# HVAC8.net
KiCad netlist of a schematic drawn in EAGLE
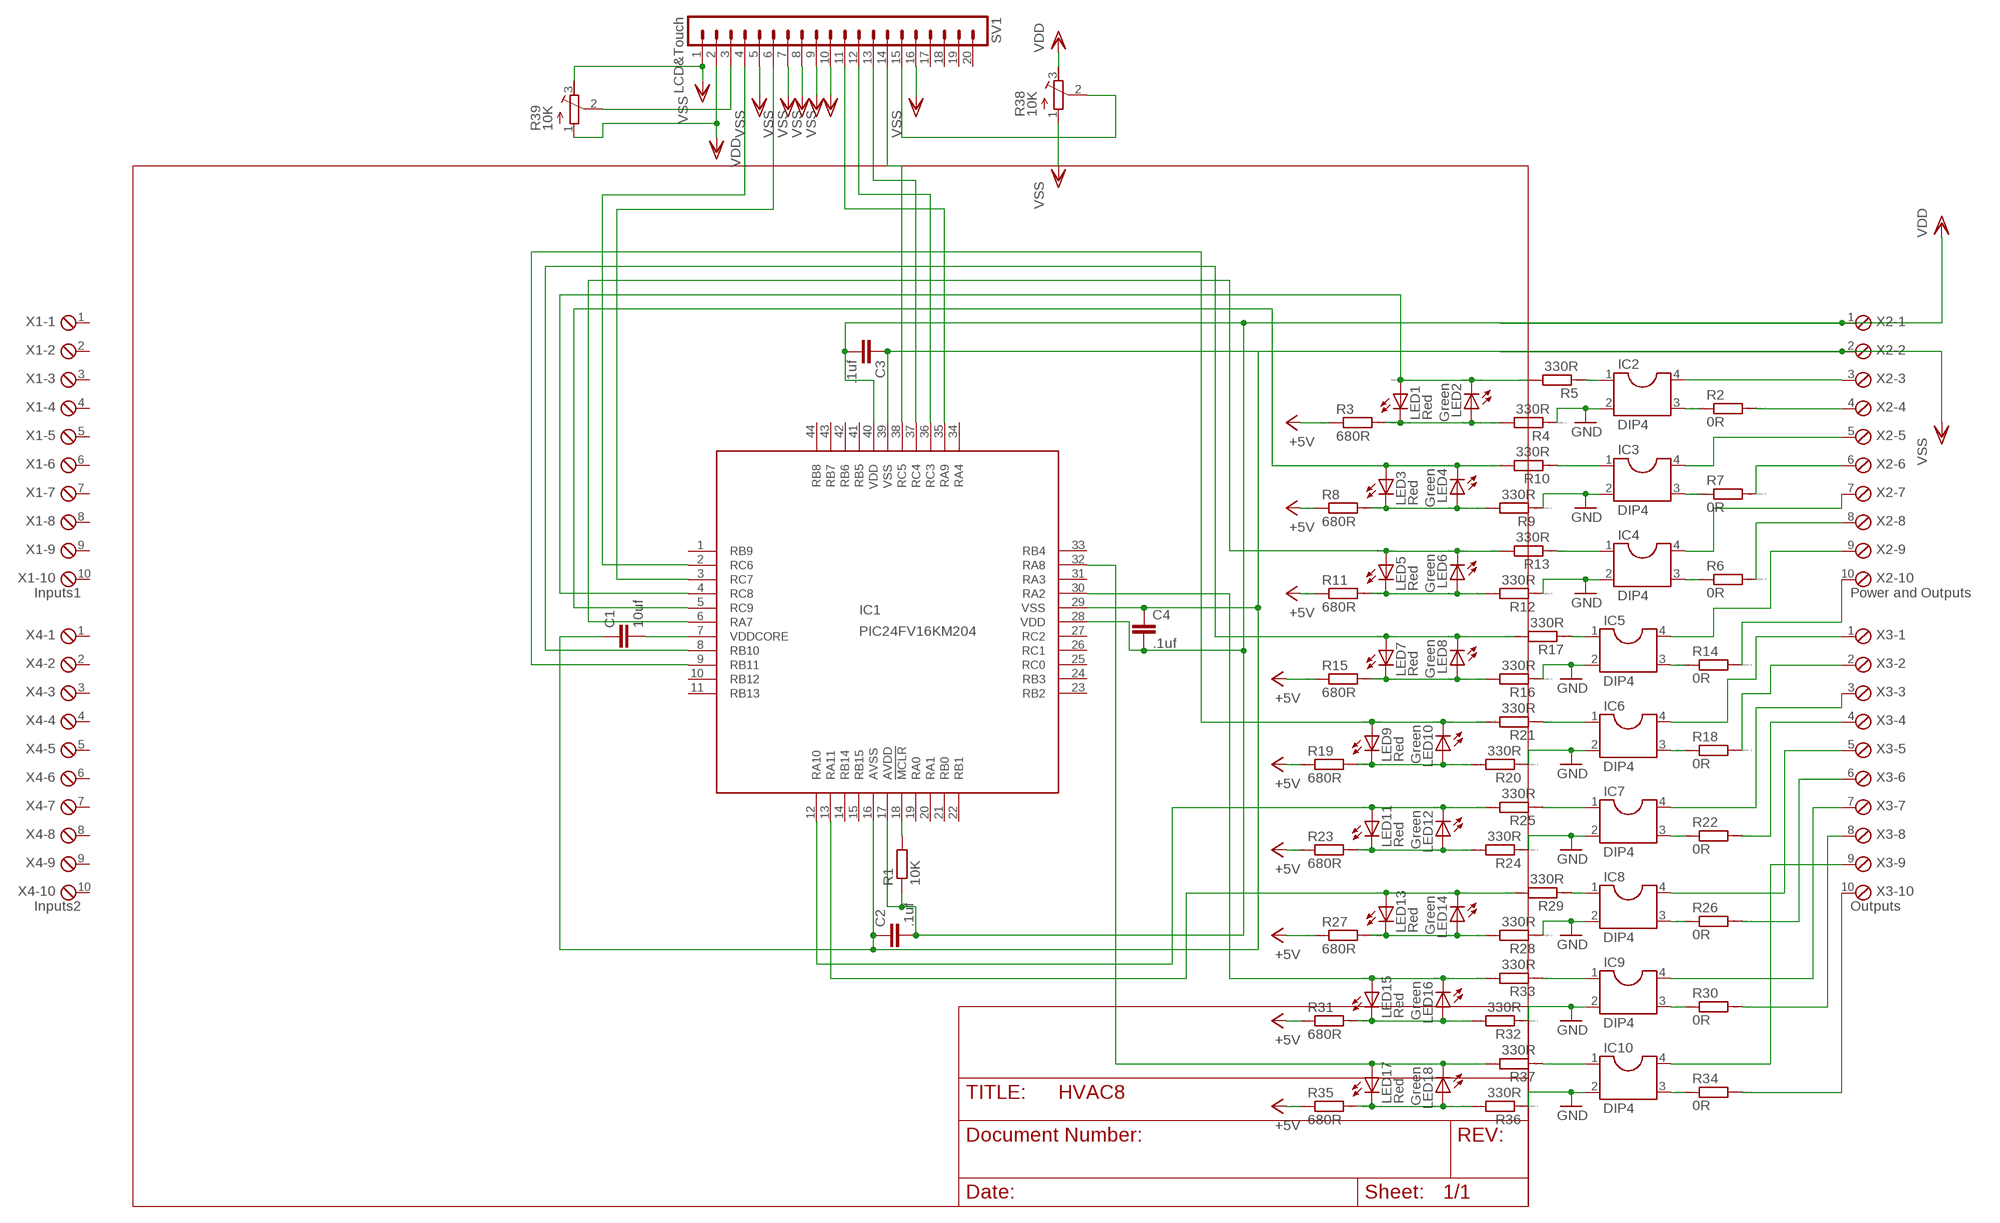
[diagram p0: schematic, sheet 1]

(export (version "E")
  (design (tool "Eeschema 10.0.6"))
  (components
    (comp (ref "C1")
      (value "10uf")
      (footprint "eagle-import:C1206")
      (libsource (lib "eagle-import") (part "C-EUC1206"))
    )
    (comp (ref "C2")
      (value ".1uf")
      (footprint "eagle-import:C1206")
      (libsource (lib "eagle-import") (part "C-EUC1206"))
    )
    (comp (ref "C3")
      (value ".1uf")
      (footprint "eagle-import:C1206")
      (libsource (lib "eagle-import") (part "C-EUC1206"))
    )
    (comp (ref "C4")
      (value ".1uf")
      (footprint "eagle-import:C1206")
      (libsource (lib "eagle-import") (part "C-EUC1206"))
    )
    (comp (ref "IC1")
      (value "PIC24FV16KM204")
      (footprint "eagle-import:TQFP44")
      (libsource (lib "eagle-import") (part "PIC24FV16KM204"))
    )
    (comp (ref "IC2")
      (value "DIP4")
      (footprint "eagle-import:SOCKET-04")
      (libsource (lib "eagle-import") (part "DIL4S"))
    )
    (comp (ref "IC3")
      (value "DIP4")
      (footprint "eagle-import:SOCKET-04")
      (libsource (lib "eagle-import") (part "DIL4S"))
    )
    (comp (ref "IC4")
      (value "DIP4")
      (footprint "eagle-import:SOCKET-04")
      (libsource (lib "eagle-import") (part "DIL4S"))
    )
    (comp (ref "IC5")
      (value "DIP4")
      (footprint "eagle-import:SOCKET-04")
      (libsource (lib "eagle-import") (part "DIL4S"))
    )
    (comp (ref "IC6")
      (value "DIP4")
      (footprint "eagle-import:SOCKET-04")
      (libsource (lib "eagle-import") (part "DIL4S"))
    )
    (comp (ref "IC7")
      (value "DIP4")
      (footprint "eagle-import:SOCKET-04")
      (libsource (lib "eagle-import") (part "DIL4S"))
    )
    (comp (ref "IC8")
      (value "DIP4")
      (footprint "eagle-import:SOCKET-04")
      (libsource (lib "eagle-import") (part "DIL4S"))
    )
    (comp (ref "IC9")
      (value "DIP4")
      (footprint "eagle-import:SOCKET-04")
      (libsource (lib "eagle-import") (part "DIL4S"))
    )
    (comp (ref "IC10")
      (value "DIP4")
      (footprint "eagle-import:SOCKET-04")
      (libsource (lib "eagle-import") (part "DIL4S"))
    )
    (comp (ref "LED1")
      (value "Red")
      (footprint "eagle-import:LED_1206")
      (libsource (lib "eagle-import") (part "LED_E"))
    )
    (comp (ref "LED2")
      (value "Green")
      (footprint "eagle-import:LED_1206")
      (libsource (lib "eagle-import") (part "LED_E"))
    )
    (comp (ref "LED3")
      (value "Red")
      (footprint "eagle-import:LED_1206")
      (libsource (lib "eagle-import") (part "LED_E"))
    )
    (comp (ref "LED4")
      (value "Green")
      (footprint "eagle-import:LED_1206")
      (libsource (lib "eagle-import") (part "LED_E"))
    )
    (comp (ref "LED5")
      (value "Red")
      (footprint "eagle-import:LED_1206")
      (libsource (lib "eagle-import") (part "LED_E"))
    )
    (comp (ref "LED6")
      (value "Green")
      (footprint "eagle-import:LED_1206")
      (libsource (lib "eagle-import") (part "LED_E"))
    )
    (comp (ref "LED7")
      (value "Red")
      (footprint "eagle-import:LED_1206")
      (libsource (lib "eagle-import") (part "LED_E"))
    )
    (comp (ref "LED8")
      (value "Green")
      (footprint "eagle-import:LED_1206")
      (libsource (lib "eagle-import") (part "LED_E"))
    )
    (comp (ref "LED9")
      (value "Red")
      (footprint "eagle-import:LED_1206")
      (libsource (lib "eagle-import") (part "LED_E"))
    )
    (comp (ref "LED10")
      (value "Green")
      (footprint "eagle-import:LED_1206")
      (libsource (lib "eagle-import") (part "LED_E"))
    )
    (comp (ref "LED11")
      (value "Red")
      (footprint "eagle-import:LED_1206")
      (libsource (lib "eagle-import") (part "LED_E"))
    )
    (comp (ref "LED12")
      (value "Green")
      (footprint "eagle-import:LED_1206")
      (libsource (lib "eagle-import") (part "LED_E"))
    )
    (comp (ref "LED13")
      (value "Red")
      (footprint "eagle-import:LED_1206")
      (libsource (lib "eagle-import") (part "LED_E"))
    )
    (comp (ref "LED14")
      (value "Green")
      (footprint "eagle-import:LED_1206")
      (libsource (lib "eagle-import") (part "LED_E"))
    )
    (comp (ref "LED15")
      (value "Red")
      (footprint "eagle-import:LED_1206")
      (libsource (lib "eagle-import") (part "LED_E"))
    )
    (comp (ref "LED16")
      (value "Green")
      (footprint "eagle-import:LED_1206")
      (libsource (lib "eagle-import") (part "LED_E"))
    )
    (comp (ref "LED17")
      (value "Red")
      (footprint "eagle-import:LED_1206")
      (libsource (lib "eagle-import") (part "LED_E"))
    )
    (comp (ref "LED18")
      (value "Green")
      (footprint "eagle-import:LED_1206")
      (libsource (lib "eagle-import") (part "LED_E"))
    )
    (comp (ref "R1")
      (value "10K")
      (footprint "eagle-import:R1206")
      (libsource (lib "eagle-import") (part "R-EU_R1206"))
    )
    (comp (ref "R2")
      (value "0R")
      (footprint "eagle-import:R1206")
      (libsource (lib "eagle-import") (part "RR1206"))
    )
    (comp (ref "R3")
      (value "680R")
      (footprint "eagle-import:R1206")
      (libsource (lib "eagle-import") (part "RR1206"))
    )
    (comp (ref "R4")
      (value "330R")
      (footprint "eagle-import:R1206")
      (libsource (lib "eagle-import") (part "RR1206"))
    )
    (comp (ref "R5")
      (value "330R")
      (footprint "eagle-import:R1206")
      (libsource (lib "eagle-import") (part "RR1206"))
    )
    (comp (ref "R6")
      (value "0R")
      (footprint "eagle-import:R1206")
      (libsource (lib "eagle-import") (part "RR1206"))
    )
    (comp (ref "R7")
      (value "0R")
      (footprint "eagle-import:R1206")
      (libsource (lib "eagle-import") (part "RR1206"))
    )
    (comp (ref "R8")
      (value "680R")
      (footprint "eagle-import:R1206")
      (libsource (lib "eagle-import") (part "RR1206"))
    )
    (comp (ref "R9")
      (value "330R")
      (footprint "eagle-import:R1206")
      (libsource (lib "eagle-import") (part "RR1206"))
    )
    (comp (ref "R10")
      (value "330R")
      (footprint "eagle-import:R1206")
      (libsource (lib "eagle-import") (part "RR1206"))
    )
    (comp (ref "R11")
      (value "680R")
      (footprint "eagle-import:R1206")
      (libsource (lib "eagle-import") (part "RR1206"))
    )
    (comp (ref "R12")
      (value "330R")
      (footprint "eagle-import:R1206")
      (libsource (lib "eagle-import") (part "RR1206"))
    )
    (comp (ref "R13")
      (value "330R")
      (footprint "eagle-import:R1206")
      (libsource (lib "eagle-import") (part "RR1206"))
    )
    (comp (ref "R14")
      (value "0R")
      (footprint "eagle-import:R1206")
      (libsource (lib "eagle-import") (part "RR1206"))
    )
    (comp (ref "R15")
      (value "680R")
      (footprint "eagle-import:R1206")
      (libsource (lib "eagle-import") (part "RR1206"))
    )
    (comp (ref "R16")
      (value "330R")
      (footprint "eagle-import:R1206")
      (libsource (lib "eagle-import") (part "RR1206"))
    )
    (comp (ref "R17")
      (value "330R")
      (footprint "eagle-import:R1206")
      (libsource (lib "eagle-import") (part "RR1206"))
    )
    (comp (ref "R18")
      (value "0R")
      (footprint "eagle-import:R1206")
      (libsource (lib "eagle-import") (part "RR1206"))
    )
    (comp (ref "R19")
      (value "680R")
      (footprint "eagle-import:R1206")
      (libsource (lib "eagle-import") (part "RR1206"))
    )
    (comp (ref "R20")
      (value "330R")
      (footprint "eagle-import:R1206")
      (libsource (lib "eagle-import") (part "RR1206"))
    )
    (comp (ref "R21")
      (value "330R")
      (footprint "eagle-import:R1206")
      (libsource (lib "eagle-import") (part "RR1206"))
    )
    (comp (ref "R22")
      (value "0R")
      (footprint "eagle-import:R1206")
      (libsource (lib "eagle-import") (part "RR1206"))
    )
    (comp (ref "R23")
      (value "680R")
      (footprint "eagle-import:R1206")
      (libsource (lib "eagle-import") (part "RR1206"))
    )
    (comp (ref "R24")
      (value "330R")
      (footprint "eagle-import:R1206")
      (libsource (lib "eagle-import") (part "RR1206"))
    )
    (comp (ref "R25")
      (value "330R")
      (footprint "eagle-import:R1206")
      (libsource (lib "eagle-import") (part "RR1206"))
    )
    (comp (ref "R26")
      (value "0R")
      (footprint "eagle-import:R1206")
      (libsource (lib "eagle-import") (part "RR1206"))
    )
    (comp (ref "R27")
      (value "680R")
      (footprint "eagle-import:R1206")
      (libsource (lib "eagle-import") (part "RR1206"))
    )
    (comp (ref "R28")
      (value "330R")
      (footprint "eagle-import:R1206")
      (libsource (lib "eagle-import") (part "RR1206"))
    )
    (comp (ref "R29")
      (value "330R")
      (footprint "eagle-import:R1206")
      (libsource (lib "eagle-import") (part "RR1206"))
    )
    (comp (ref "R30")
      (value "0R")
      (footprint "eagle-import:R1206")
      (libsource (lib "eagle-import") (part "RR1206"))
    )
    (comp (ref "R31")
      (value "680R")
      (footprint "eagle-import:R1206")
      (libsource (lib "eagle-import") (part "RR1206"))
    )
    (comp (ref "R32")
      (value "330R")
      (footprint "eagle-import:R1206")
      (libsource (lib "eagle-import") (part "RR1206"))
    )
    (comp (ref "R33")
      (value "330R")
      (footprint "eagle-import:R1206")
      (libsource (lib "eagle-import") (part "RR1206"))
    )
    (comp (ref "R34")
      (value "0R")
      (footprint "eagle-import:R1206")
      (libsource (lib "eagle-import") (part "RR1206"))
    )
    (comp (ref "R35")
      (value "680R")
      (footprint "eagle-import:R1206")
      (libsource (lib "eagle-import") (part "RR1206"))
    )
    (comp (ref "R36")
      (value "330R")
      (footprint "eagle-import:R1206")
      (libsource (lib "eagle-import") (part "RR1206"))
    )
    (comp (ref "R37")
      (value "330R")
      (footprint "eagle-import:R1206")
      (libsource (lib "eagle-import") (part "RR1206"))
    )
    (comp (ref "R38")
      (value "10K")
      (footprint "eagle-import:RTRIM3296W")
      (libsource (lib "eagle-import") (part "R-TRIMM3296W"))
    )
    (comp (ref "R39")
      (value "10K")
      (footprint "eagle-import:RTRIM3296W")
      (libsource (lib "eagle-import") (part "R-TRIMM3296W"))
    )
    (comp (ref "SV1")
      (value "LCD&Touch")
      (footprint "eagle-import:MA20-1")
      (libsource (lib "eagle-import") (part "MA20-1"))
    )
    (comp (ref "X1")
      (value "Inputs1")
      (footprint "eagle-import:10POL254")
      (libsource (lib "eagle-import") (part "MPT10"))
    )
    (comp (ref "X2")
      (value "Power and Outputs")
      (footprint "eagle-import:10POL254")
      (libsource (lib "eagle-import") (part "MPT10"))
    )
    (comp (ref "X3")
      (value "Outputs")
      (footprint "eagle-import:10POL254")
      (libsource (lib "eagle-import") (part "MPT10"))
    )
    (comp (ref "X4")
      (value "Inputs2")
      (footprint "eagle-import:10POL254")
      (libsource (lib "eagle-import") (part "MPT10"))
    )
  )
  (nets
    (net (code "1") (name "+5V") (class "Default")
      (node (ref "R11") (pin "1") (pinfunction "1_1") (pintype "passive"))
      (node (ref "R15") (pin "1") (pinfunction "1_1") (pintype "passive"))
      (node (ref "R19") (pin "1") (pinfunction "1_1") (pintype "passive"))
      (node (ref "R23") (pin "1") (pinfunction "1_1") (pintype "passive"))
      (node (ref "R27") (pin "1") (pinfunction "1_1") (pintype "passive"))
      (node (ref "R3") (pin "1") (pinfunction "1_1") (pintype "passive"))
      (node (ref "R31") (pin "1") (pinfunction "1_1") (pintype "passive"))
      (node (ref "R35") (pin "1") (pinfunction "1_1") (pintype "passive"))
      (node (ref "R8") (pin "1") (pinfunction "1_1") (pintype "passive"))
    )
    (net (code "2") (name "GND") (class "Default")
      (node (ref "IC10") (pin "2") (pinfunction "2_2") (pintype "passive"))
      (node (ref "IC2") (pin "2") (pinfunction "2_2") (pintype "passive"))
      (node (ref "IC3") (pin "2") (pinfunction "2_2") (pintype "passive"))
      (node (ref "IC4") (pin "2") (pinfunction "2_2") (pintype "passive"))
      (node (ref "IC5") (pin "2") (pinfunction "2_2") (pintype "passive"))
      (node (ref "IC6") (pin "2") (pinfunction "2_2") (pintype "passive"))
      (node (ref "IC7") (pin "2") (pinfunction "2_2") (pintype "passive"))
      (node (ref "IC8") (pin "2") (pinfunction "2_2") (pintype "passive"))
      (node (ref "IC9") (pin "2") (pinfunction "2_2") (pintype "passive"))
      (node (ref "R12") (pin "1") (pinfunction "1_1") (pintype "passive"))
      (node (ref "R16") (pin "1") (pinfunction "1_1") (pintype "passive"))
      (node (ref "R20") (pin "1") (pinfunction "1_1") (pintype "passive"))
      (node (ref "R24") (pin "1") (pinfunction "1_1") (pintype "passive"))
      (node (ref "R28") (pin "1") (pinfunction "1_1") (pintype "passive"))
      (node (ref "R32") (pin "1") (pinfunction "1_1") (pintype "passive"))
      (node (ref "R36") (pin "1") (pinfunction "1_1") (pintype "passive"))
      (node (ref "R4") (pin "1") (pinfunction "1_1") (pintype "passive"))
      (node (ref "R9") (pin "1") (pinfunction "1_1") (pintype "passive"))
    )
    (net (code "3") (name "Net-(IC1-RA2)") (class "Default")
      (node (ref "IC1") (pin "30") (pinfunction "RA2_30") (pintype "bidirectional"))
      (node (ref "LED15") (pin "A") (pinfunction "A_A") (pintype "passive"))
      (node (ref "LED16") (pin "C") (pinfunction "C_C") (pintype "passive"))
      (node (ref "R33") (pin "2") (pinfunction "2_2") (pintype "passive"))
    )
    (net (code "4") (name "Net-(IC1-RA7)") (class "Default")
      (node (ref "IC1") (pin "6") (pinfunction "RA7_6") (pintype "bidirectional"))
      (node (ref "LED5") (pin "A") (pinfunction "A_A") (pintype "passive"))
      (node (ref "LED6") (pin "C") (pinfunction "C_C") (pintype "passive"))
      (node (ref "R13") (pin "2") (pinfunction "2_2") (pintype "passive"))
    )
    (net (code "5") (name "Net-(IC1-RA8)") (class "Default")
      (node (ref "IC1") (pin "32") (pinfunction "RA8_32") (pintype "bidirectional"))
      (node (ref "LED17") (pin "A") (pinfunction "A_A") (pintype "passive"))
      (node (ref "LED18") (pin "C") (pinfunction "C_C") (pintype "passive"))
      (node (ref "R37") (pin "2") (pinfunction "2_2") (pintype "passive"))
    )
    (net (code "6") (name "Net-(IC1-RA9)") (class "Default")
      (node (ref "IC1") (pin "35") (pinfunction "RA9_35") (pintype "bidirectional"))
      (node (ref "SV1") (pin "11") (pinfunction "11_11") (pintype "passive"))
    )
    (net (code "7") (name "Net-(IC1-RA10)") (class "Default")
      (node (ref "IC1") (pin "12") (pinfunction "RA10_12") (pintype "bidirectional"))
      (node (ref "LED11") (pin "A") (pinfunction "A_A") (pintype "passive"))
      (node (ref "LED12") (pin "C") (pinfunction "C_C") (pintype "passive"))
      (node (ref "R25") (pin "2") (pinfunction "2_2") (pintype "passive"))
    )
    (net (code "8") (name "Net-(IC1-RA11)") (class "Default")
      (node (ref "IC1") (pin "13") (pinfunction "RA11_13") (pintype "bidirectional"))
      (node (ref "LED13") (pin "A") (pinfunction "A_A") (pintype "passive"))
      (node (ref "LED14") (pin "C") (pinfunction "C_C") (pintype "passive"))
      (node (ref "R29") (pin "2") (pinfunction "2_2") (pintype "passive"))
    )
    (net (code "9") (name "Net-(IC1-RB10)") (class "Default")
      (node (ref "IC1") (pin "8") (pinfunction "RB10_8") (pintype "bidirectional"))
      (node (ref "LED7") (pin "A") (pinfunction "A_A") (pintype "passive"))
      (node (ref "LED8") (pin "C") (pinfunction "C_C") (pintype "passive"))
      (node (ref "R17") (pin "2") (pinfunction "2_2") (pintype "passive"))
    )
    (net (code "10") (name "Net-(IC1-RB11)") (class "Default")
      (node (ref "IC1") (pin "9") (pinfunction "RB11_9") (pintype "bidirectional"))
      (node (ref "LED10") (pin "C") (pinfunction "C_C") (pintype "passive"))
      (node (ref "LED9") (pin "A") (pinfunction "A_A") (pintype "passive"))
      (node (ref "R21") (pin "2") (pinfunction "2_2") (pintype "passive"))
    )
    (net (code "11") (name "Net-(IC1-RC3)") (class "Default")
      (node (ref "IC1") (pin "36") (pinfunction "RC3_36") (pintype "bidirectional"))
      (node (ref "SV1") (pin "12") (pinfunction "12_12") (pintype "passive"))
    )
    (net (code "12") (name "Net-(IC1-RC4)") (class "Default")
      (node (ref "IC1") (pin "37") (pinfunction "RC4_37") (pintype "bidirectional"))
      (node (ref "SV1") (pin "13") (pinfunction "13_13") (pintype "passive"))
    )
    (net (code "13") (name "Net-(IC1-RC5)") (class "Default")
      (node (ref "IC1") (pin "38") (pinfunction "RC5_38") (pintype "bidirectional"))
      (node (ref "SV1") (pin "14") (pinfunction "14_14") (pintype "passive"))
    )
    (net (code "14") (name "Net-(IC1-RC6)") (class "Default")
      (node (ref "IC1") (pin "2") (pinfunction "RC6_2") (pintype "bidirectional"))
      (node (ref "SV1") (pin "4") (pinfunction "4_4") (pintype "passive"))
    )
    (net (code "15") (name "Net-(IC1-RC7)") (class "Default")
      (node (ref "IC1") (pin "3") (pinfunction "RC7_3") (pintype "bidirectional"))
      (node (ref "SV1") (pin "6") (pinfunction "6_6") (pintype "passive"))
    )
    (net (code "16") (name "Net-(IC1-RC8)") (class "Default")
      (node (ref "IC1") (pin "4") (pinfunction "RC8_4") (pintype "bidirectional"))
      (node (ref "LED1") (pin "A") (pinfunction "A_A") (pintype "passive"))
      (node (ref "LED2") (pin "C") (pinfunction "C_C") (pintype "passive"))
      (node (ref "R5") (pin "2") (pinfunction "2_2") (pintype "passive"))
    )
    (net (code "17") (name "Net-(IC1-RC9)") (class "Default")
      (node (ref "IC1") (pin "5") (pinfunction "RC9_5") (pintype "bidirectional"))
      (node (ref "LED3") (pin "A") (pinfunction "A_A") (pintype "passive"))
      (node (ref "LED4") (pin "C") (pinfunction "C_C") (pintype "passive"))
      (node (ref "R10") (pin "2") (pinfunction "2_2") (pintype "passive"))
    )
    (net (code "18") (name "Net-(IC1-VDDCORE)") (class "Default")
      (node (ref "C1") (pin "2") (pinfunction "2_2") (pintype "passive"))
      (node (ref "IC1") (pin "7") (pinfunction "VDDCORE_7") (pintype "power_in"))
    )
    (net (code "19") (name "Net-(IC1-~{MCLR})") (class "Default")
      (node (ref "IC1") (pin "18") (pinfunction "~{MCLR}_18") (pintype "bidirectional"))
      (node (ref "R1") (pin "2") (pinfunction "2_2") (pintype "passive"))
    )
    (net (code "20") (name "Net-(IC2-Pad1)") (class "Default")
      (node (ref "IC2") (pin "1") (pinfunction "1_1") (pintype "passive"))
      (node (ref "R5") (pin "1") (pinfunction "1_1") (pintype "passive"))
    )
    (net (code "21") (name "Net-(IC2-Pad3)") (class "Default")
      (node (ref "IC2") (pin "3") (pinfunction "3_3") (pintype "passive"))
      (node (ref "R2") (pin "1") (pinfunction "1_1") (pintype "passive"))
    )
    (net (code "22") (name "Net-(IC3-Pad1)") (class "Default")
      (node (ref "IC3") (pin "1") (pinfunction "1_1") (pintype "passive"))
      (node (ref "R10") (pin "1") (pinfunction "1_1") (pintype "passive"))
    )
    (net (code "23") (name "Net-(IC3-Pad3)") (class "Default")
      (node (ref "IC3") (pin "3") (pinfunction "3_3") (pintype "passive"))
      (node (ref "R7") (pin "1") (pinfunction "1_1") (pintype "passive"))
    )
    (net (code "24") (name "Net-(IC4-Pad1)") (class "Default")
      (node (ref "IC4") (pin "1") (pinfunction "1_1") (pintype "passive"))
      (node (ref "R13") (pin "1") (pinfunction "1_1") (pintype "passive"))
    )
    (net (code "25") (name "Net-(IC4-Pad3)") (class "Default")
      (node (ref "IC4") (pin "3") (pinfunction "3_3") (pintype "passive"))
      (node (ref "R6") (pin "1") (pinfunction "1_1") (pintype "passive"))
    )
    (net (code "26") (name "Net-(IC5-Pad1)") (class "Default")
      (node (ref "IC5") (pin "1") (pinfunction "1_1") (pintype "passive"))
      (node (ref "R17") (pin "1") (pinfunction "1_1") (pintype "passive"))
    )
    (net (code "27") (name "Net-(IC5-Pad3)") (class "Default")
      (node (ref "IC5") (pin "3") (pinfunction "3_3") (pintype "passive"))
      (node (ref "R14") (pin "1") (pinfunction "1_1") (pintype "passive"))
    )
    (net (code "28") (name "Net-(IC6-Pad1)") (class "Default")
      (node (ref "IC6") (pin "1") (pinfunction "1_1") (pintype "passive"))
      (node (ref "R21") (pin "1") (pinfunction "1_1") (pintype "passive"))
    )
    (net (code "29") (name "Net-(IC6-Pad3)") (class "Default")
      (node (ref "IC6") (pin "3") (pinfunction "3_3") (pintype "passive"))
      (node (ref "R18") (pin "1") (pinfunction "1_1") (pintype "passive"))
    )
    (net (code "30") (name "Net-(IC6-Pad4)") (class "Default")
      (node (ref "IC6") (pin "4") (pinfunction "4_4") (pintype "passive"))
      (node (ref "X3") (pin "1") (pinfunction "1_1") (pintype "passive"))
    )
    (net (code "31") (name "Net-(IC7-Pad1)") (class "Default")
      (node (ref "IC7") (pin "1") (pinfunction "1_1") (pintype "passive"))
      (node (ref "R25") (pin "1") (pinfunction "1_1") (pintype "passive"))
    )
    (net (code "32") (name "Net-(IC7-Pad3)") (class "Default")
      (node (ref "IC7") (pin "3") (pinfunction "3_3") (pintype "passive"))
      (node (ref "R22") (pin "1") (pinfunction "1_1") (pintype "passive"))
    )
    (net (code "33") (name "Net-(IC8-Pad1)") (class "Default")
      (node (ref "IC8") (pin "1") (pinfunction "1_1") (pintype "passive"))
      (node (ref "R29") (pin "1") (pinfunction "1_1") (pintype "passive"))
    )
    (net (code "34") (name "Net-(IC8-Pad3)") (class "Default")
      (node (ref "IC8") (pin "3") (pinfunction "3_3") (pintype "passive"))
      (node (ref "R26") (pin "1") (pinfunction "1_1") (pintype "passive"))
    )
    (net (code "35") (name "Net-(IC9-Pad1)") (class "Default")
      (node (ref "IC9") (pin "1") (pinfunction "1_1") (pintype "passive"))
      (node (ref "R33") (pin "1") (pinfunction "1_1") (pintype "passive"))
    )
    (net (code "36") (name "Net-(IC9-Pad3)") (class "Default")
      (node (ref "IC9") (pin "3") (pinfunction "3_3") (pintype "passive"))
      (node (ref "R30") (pin "1") (pinfunction "1_1") (pintype "passive"))
    )
    (net (code "37") (name "Net-(IC10-Pad1)") (class "Default")
      (node (ref "IC10") (pin "1") (pinfunction "1_1") (pintype "passive"))
      (node (ref "R37") (pin "1") (pinfunction "1_1") (pintype "passive"))
    )
    (net (code "38") (name "Net-(IC10-Pad3)") (class "Default")
      (node (ref "IC10") (pin "3") (pinfunction "3_3") (pintype "passive"))
      (node (ref "R34") (pin "1") (pinfunction "1_1") (pintype "passive"))
    )
    (net (code "39") (name "Net-(LED1-PadC)") (class "Default")
      (node (ref "LED1") (pin "C") (pinfunction "C_C") (pintype "passive"))
      (node (ref "LED2") (pin "A") (pinfunction "A_A") (pintype "passive"))
      (node (ref "R3") (pin "2") (pinfunction "2_2") (pintype "passive"))
      (node (ref "R4") (pin "2") (pinfunction "2_2") (pintype "passive"))
    )
    (net (code "40") (name "Net-(LED3-PadC)") (class "Default")
      (node (ref "LED3") (pin "C") (pinfunction "C_C") (pintype "passive"))
      (node (ref "LED4") (pin "A") (pinfunction "A_A") (pintype "passive"))
      (node (ref "R8") (pin "2") (pinfunction "2_2") (pintype "passive"))
      (node (ref "R9") (pin "2") (pinfunction "2_2") (pintype "passive"))
    )
    (net (code "41") (name "Net-(LED5-PadC)") (class "Default")
      (node (ref "LED5") (pin "C") (pinfunction "C_C") (pintype "passive"))
      (node (ref "LED6") (pin "A") (pinfunction "A_A") (pintype "passive"))
      (node (ref "R11") (pin "2") (pinfunction "2_2") (pintype "passive"))
      (node (ref "R12") (pin "2") (pinfunction "2_2") (pintype "passive"))
    )
    (net (code "42") (name "Net-(LED7-PadC)") (class "Default")
      (node (ref "LED7") (pin "C") (pinfunction "C_C") (pintype "passive"))
      (node (ref "LED8") (pin "A") (pinfunction "A_A") (pintype "passive"))
      (node (ref "R15") (pin "2") (pinfunction "2_2") (pintype "passive"))
      (node (ref "R16") (pin "2") (pinfunction "2_2") (pintype "passive"))
    )
    (net (code "43") (name "Net-(LED10-PadA)") (class "Default")
      (node (ref "LED10") (pin "A") (pinfunction "A_A") (pintype "passive"))
      (node (ref "LED9") (pin "C") (pinfunction "C_C") (pintype "passive"))
      (node (ref "R19") (pin "2") (pinfunction "2_2") (pintype "passive"))
      (node (ref "R20") (pin "2") (pinfunction "2_2") (pintype "passive"))
    )
    (net (code "44") (name "Net-(LED11-PadC)") (class "Default")
      (node (ref "LED11") (pin "C") (pinfunction "C_C") (pintype "passive"))
      (node (ref "LED12") (pin "A") (pinfunction "A_A") (pintype "passive"))
      (node (ref "R23") (pin "2") (pinfunction "2_2") (pintype "passive"))
      (node (ref "R24") (pin "2") (pinfunction "2_2") (pintype "passive"))
    )
    (net (code "45") (name "Net-(LED13-PadC)") (class "Default")
      (node (ref "LED13") (pin "C") (pinfunction "C_C") (pintype "passive"))
      (node (ref "LED14") (pin "A") (pinfunction "A_A") (pintype "passive"))
      (node (ref "R27") (pin "2") (pinfunction "2_2") (pintype "passive"))
      (node (ref "R28") (pin "2") (pinfunction "2_2") (pintype "passive"))
    )
    (net (code "46") (name "Net-(LED15-PadC)") (class "Default")
      (node (ref "LED15") (pin "C") (pinfunction "C_C") (pintype "passive"))
      (node (ref "LED16") (pin "A") (pinfunction "A_A") (pintype "passive"))
      (node (ref "R31") (pin "2") (pinfunction "2_2") (pintype "passive"))
      (node (ref "R32") (pin "2") (pinfunction "2_2") (pintype "passive"))
    )
    (net (code "47") (name "Net-(LED17-PadC)") (class "Default")
      (node (ref "LED17") (pin "C") (pinfunction "C_C") (pintype "passive"))
      (node (ref "LED18") (pin "A") (pinfunction "A_A") (pintype "passive"))
      (node (ref "R35") (pin "2") (pinfunction "2_2") (pintype "passive"))
      (node (ref "R36") (pin "2") (pinfunction "2_2") (pintype "passive"))
    )
    (net (code "48") (name "Net-(R38-S)") (class "Default")
      (node (ref "R38") (pin "2") (pinfunction "S_2") (pintype "passive"))
      (node (ref "SV1") (pin "15") (pinfunction "15_15") (pintype "passive"))
    )
    (net (code "49") (name "Net-(R39-S)") (class "Default")
      (node (ref "R39") (pin "2") (pinfunction "S_2") (pintype "passive"))
      (node (ref "SV1") (pin "3") (pinfunction "3_3") (pintype "passive"))
    )
    (net (code "50") (name "Net-(X2B-1)") (class "Default")
      (node (ref "R14") (pin "2") (pinfunction "2_2") (pintype "passive"))
      (node (ref "X2") (pin "10") (pinfunction "1_10") (pintype "passive"))
    )
    (net (code "51") (name "Net-(X2D-1)") (class "Default")
      (node (ref "IC2") (pin "4") (pinfunction "4_4") (pintype "passive"))
      (node (ref "X2") (pin "3") (pinfunction "1_3") (pintype "passive"))
    )
    (net (code "52") (name "Net-(X2E-1)") (class "Default")
      (node (ref "R2") (pin "2") (pinfunction "2_2") (pintype "passive"))
      (node (ref "X2") (pin "4") (pinfunction "1_4") (pintype "passive"))
    )
    (net (code "53") (name "Net-(X2F-1)") (class "Default")
      (node (ref "IC3") (pin "4") (pinfunction "4_4") (pintype "passive"))
      (node (ref "X2") (pin "5") (pinfunction "1_5") (pintype "passive"))
    )
    (net (code "54") (name "Net-(X2G-1)") (class "Default")
      (node (ref "R7") (pin "2") (pinfunction "2_2") (pintype "passive"))
      (node (ref "X2") (pin "6") (pinfunction "1_6") (pintype "passive"))
    )
    (net (code "55") (name "Net-(X2H-1)") (class "Default")
      (node (ref "IC4") (pin "4") (pinfunction "4_4") (pintype "passive"))
      (node (ref "X2") (pin "7") (pinfunction "1_7") (pintype "passive"))
    )
    (net (code "56") (name "Net-(X2I-1)") (class "Default")
      (node (ref "R6") (pin "2") (pinfunction "2_2") (pintype "passive"))
      (node (ref "X2") (pin "8") (pinfunction "1_8") (pintype "passive"))
    )
    (net (code "57") (name "Net-(X2J-1)") (class "Default")
      (node (ref "IC5") (pin "4") (pinfunction "4_4") (pintype "passive"))
      (node (ref "X2") (pin "9") (pinfunction "1_9") (pintype "passive"))
    )
    (net (code "58") (name "Net-(X3B-1)") (class "Default")
      (node (ref "R34") (pin "2") (pinfunction "2_2") (pintype "passive"))
      (node (ref "X3") (pin "10") (pinfunction "1_10") (pintype "passive"))
    )
    (net (code "59") (name "Net-(X3C-1)") (class "Default")
      (node (ref "R18") (pin "2") (pinfunction "2_2") (pintype "passive"))
      (node (ref "X3") (pin "2") (pinfunction "1_2") (pintype "passive"))
    )
    (net (code "60") (name "Net-(X3D-1)") (class "Default")
      (node (ref "IC7") (pin "4") (pinfunction "4_4") (pintype "passive"))
      (node (ref "X3") (pin "3") (pinfunction "1_3") (pintype "passive"))
    )
    (net (code "61") (name "Net-(X3E-1)") (class "Default")
      (node (ref "R22") (pin "2") (pinfunction "2_2") (pintype "passive"))
      (node (ref "X3") (pin "4") (pinfunction "1_4") (pintype "passive"))
    )
    (net (code "62") (name "Net-(X3F-1)") (class "Default")
      (node (ref "IC8") (pin "4") (pinfunction "4_4") (pintype "passive"))
      (node (ref "X3") (pin "5") (pinfunction "1_5") (pintype "passive"))
    )
    (net (code "63") (name "Net-(X3G-1)") (class "Default")
      (node (ref "R26") (pin "2") (pinfunction "2_2") (pintype "passive"))
      (node (ref "X3") (pin "6") (pinfunction "1_6") (pintype "passive"))
    )
    (net (code "64") (name "Net-(X3H-1)") (class "Default")
      (node (ref "IC9") (pin "4") (pinfunction "4_4") (pintype "passive"))
      (node (ref "X3") (pin "7") (pinfunction "1_7") (pintype "passive"))
    )
    (net (code "65") (name "Net-(X3I-1)") (class "Default")
      (node (ref "R30") (pin "2") (pinfunction "2_2") (pintype "passive"))
      (node (ref "X3") (pin "8") (pinfunction "1_8") (pintype "passive"))
    )
    (net (code "66") (name "Net-(X3J-1)") (class "Default")
      (node (ref "IC10") (pin "4") (pinfunction "4_4") (pintype "passive"))
      (node (ref "X3") (pin "9") (pinfunction "1_9") (pintype "passive"))
    )
    (net (code "67") (name "VDD") (class "Default")
      (node (ref "C2") (pin "2") (pinfunction "2_2") (pintype "passive"))
      (node (ref "C3") (pin "2") (pinfunction "2_2") (pintype "passive"))
      (node (ref "C4") (pin "2") (pinfunction "2_2") (pintype "passive"))
      (node (ref "IC1") (pin "17") (pinfunction "AVDD_17") (pintype "power_in"))
      (node (ref "IC1") (pin "28") (pinfunction "VDD_28") (pintype "power_in"))
      (node (ref "IC1") (pin "40") (pinfunction "VDD_40") (pintype "power_in"))
      (node (ref "R1") (pin "1") (pinfunction "1_1") (pintype "passive"))
      (node (ref "R38") (pin "3") (pinfunction "E_3") (pintype "passive"))
      (node (ref "R39") (pin "1") (pinfunction "A_1") (pintype "passive"))
      (node (ref "SV1") (pin "2") (pinfunction "2_2") (pintype "passive"))
      (node (ref "X2") (pin "1") (pinfunction "1_1") (pintype "passive"))
    )
    (net (code "68") (name "VSS") (class "Default")
      (node (ref "C1") (pin "1") (pinfunction "1_1") (pintype "passive"))
      (node (ref "C2") (pin "1") (pinfunction "1_1") (pintype "passive"))
      (node (ref "C3") (pin "1") (pinfunction "1_1") (pintype "passive"))
      (node (ref "C4") (pin "1") (pinfunction "1_1") (pintype "passive"))
      (node (ref "IC1") (pin "16") (pinfunction "AVSS_16") (pintype "power_in"))
      (node (ref "IC1") (pin "29") (pinfunction "VSS_29") (pintype "power_in"))
      (node (ref "IC1") (pin "39") (pinfunction "VSS_39") (pintype "power_in"))
      (node (ref "R38") (pin "1") (pinfunction "A_1") (pintype "passive"))
      (node (ref "R39") (pin "3") (pinfunction "E_3") (pintype "passive"))
      (node (ref "SV1") (pin "1") (pinfunction "1_1") (pintype "passive"))
      (node (ref "SV1") (pin "10") (pinfunction "10_10") (pintype "passive"))
      (node (ref "SV1") (pin "16") (pinfunction "16_16") (pintype "passive"))
      (node (ref "SV1") (pin "5") (pinfunction "5_5") (pintype "passive"))
      (node (ref "SV1") (pin "7") (pinfunction "7_7") (pintype "passive"))
      (node (ref "SV1") (pin "8") (pinfunction "8_8") (pintype "passive"))
      (node (ref "SV1") (pin "9") (pinfunction "9_9") (pintype "passive"))
      (node (ref "X2") (pin "2") (pinfunction "1_2") (pintype "passive"))
    )
    (net (code "69") (name "unconnected-(IC1-RA0-Pad19)") (class "Default")
      (node (ref "IC1") (pin "19") (pinfunction "RA0_19") (pintype "bidirectional"))
    )
    (net (code "70") (name "unconnected-(IC1-RA1-Pad20)") (class "Default")
      (node (ref "IC1") (pin "20") (pinfunction "RA1_20") (pintype "bidirectional"))
    )
    (net (code "71") (name "unconnected-(IC1-RA3-Pad31)") (class "Default")
      (node (ref "IC1") (pin "31") (pinfunction "RA3_31") (pintype "bidirectional"))
    )
    (net (code "72") (name "unconnected-(IC1-RA4-Pad34)") (class "Default")
      (node (ref "IC1") (pin "34") (pinfunction "RA4_34") (pintype "bidirectional"))
    )
    (net (code "73") (name "unconnected-(IC1-RB0-Pad21)") (class "Default")
      (node (ref "IC1") (pin "21") (pinfunction "RB0_21") (pintype "bidirectional"))
    )
    (net (code "74") (name "unconnected-(IC1-RB1-Pad22)") (class "Default")
      (node (ref "IC1") (pin "22") (pinfunction "RB1_22") (pintype "bidirectional"))
    )
    (net (code "75") (name "unconnected-(IC1-RB2-Pad23)") (class "Default")
      (node (ref "IC1") (pin "23") (pinfunction "RB2_23") (pintype "bidirectional"))
    )
    (net (code "76") (name "unconnected-(IC1-RB3-Pad24)") (class "Default")
      (node (ref "IC1") (pin "24") (pinfunction "RB3_24") (pintype "bidirectional"))
    )
    (net (code "77") (name "unconnected-(IC1-RB4-Pad33)") (class "Default")
      (node (ref "IC1") (pin "33") (pinfunction "RB4_33") (pintype "bidirectional"))
    )
    (net (code "78") (name "unconnected-(IC1-RB5-Pad41)") (class "Default")
      (node (ref "IC1") (pin "41") (pinfunction "RB5_41") (pintype "bidirectional"))
    )
    (net (code "79") (name "unconnected-(IC1-RB6-Pad42)") (class "Default")
      (node (ref "IC1") (pin "42") (pinfunction "RB6_42") (pintype "bidirectional"))
    )
    (net (code "80") (name "unconnected-(IC1-RB7-Pad43)") (class "Default")
      (node (ref "IC1") (pin "43") (pinfunction "RB7_43") (pintype "bidirectional"))
    )
    (net (code "81") (name "unconnected-(IC1-RB8-Pad44)") (class "Default")
      (node (ref "IC1") (pin "44") (pinfunction "RB8_44") (pintype "bidirectional"))
    )
    (net (code "82") (name "unconnected-(IC1-RB9-Pad1)") (class "Default")
      (node (ref "IC1") (pin "1") (pinfunction "RB9_1") (pintype "bidirectional"))
    )
    (net (code "83") (name "unconnected-(IC1-RB12-Pad10)") (class "Default")
      (node (ref "IC1") (pin "10") (pinfunction "RB12_10") (pintype "bidirectional"))
    )
    (net (code "84") (name "unconnected-(IC1-RB13-Pad11)") (class "Default")
      (node (ref "IC1") (pin "11") (pinfunction "RB13_11") (pintype "bidirectional"))
    )
    (net (code "85") (name "unconnected-(IC1-RB14-Pad14)") (class "Default")
      (node (ref "IC1") (pin "14") (pinfunction "RB14_14") (pintype "bidirectional"))
    )
    (net (code "86") (name "unconnected-(IC1-RB15-Pad15)") (class "Default")
      (node (ref "IC1") (pin "15") (pinfunction "RB15_15") (pintype "bidirectional"))
    )
    (net (code "87") (name "unconnected-(IC1-RC0-Pad25)") (class "Default")
      (node (ref "IC1") (pin "25") (pinfunction "RC0_25") (pintype "bidirectional"))
    )
    (net (code "88") (name "unconnected-(IC1-RC1-Pad26)") (class "Default")
      (node (ref "IC1") (pin "26") (pinfunction "RC1_26") (pintype "bidirectional"))
    )
    (net (code "89") (name "unconnected-(IC1-RC2-Pad27)") (class "Default")
      (node (ref "IC1") (pin "27") (pinfunction "RC2_27") (pintype "bidirectional"))
    )
    (net (code "90") (name "unconnected-(SV1-Pad17)") (class "Default")
      (node (ref "SV1") (pin "17") (pinfunction "17_17") (pintype "passive"))
    )
    (net (code "91") (name "unconnected-(SV1-Pad18)") (class "Default")
      (node (ref "SV1") (pin "18") (pinfunction "18_18") (pintype "passive"))
    )
    (net (code "92") (name "unconnected-(SV1-Pad19)") (class "Default")
      (node (ref "SV1") (pin "19") (pinfunction "19_19") (pintype "passive"))
    )
    (net (code "93") (name "unconnected-(SV1-Pad20)") (class "Default")
      (node (ref "SV1") (pin "20") (pinfunction "20_20") (pintype "passive"))
    )
    (net (code "94") (name "unconnected-(X1-Pad1)") (class "Default")
      (node (ref "X1") (pin "1") (pinfunction "1_1") (pintype "passive"))
    )
    (net (code "95") (name "unconnected-(X1B-1-Pad10)") (class "Default")
      (node (ref "X1") (pin "10") (pinfunction "1_10") (pintype "passive"))
    )
    (net (code "96") (name "unconnected-(X1C-1-Pad2)") (class "Default")
      (node (ref "X1") (pin "2") (pinfunction "1_2") (pintype "passive"))
    )
    (net (code "97") (name "unconnected-(X1D-1-Pad3)") (class "Default")
      (node (ref "X1") (pin "3") (pinfunction "1_3") (pintype "passive"))
    )
    (net (code "98") (name "unconnected-(X1E-1-Pad4)") (class "Default")
      (node (ref "X1") (pin "4") (pinfunction "1_4") (pintype "passive"))
    )
    (net (code "99") (name "unconnected-(X1F-1-Pad5)") (class "Default")
      (node (ref "X1") (pin "5") (pinfunction "1_5") (pintype "passive"))
    )
    (net (code "100") (name "unconnected-(X1G-1-Pad6)") (class "Default")
      (node (ref "X1") (pin "6") (pinfunction "1_6") (pintype "passive"))
    )
    (net (code "101") (name "unconnected-(X1H-1-Pad7)") (class "Default")
      (node (ref "X1") (pin "7") (pinfunction "1_7") (pintype "passive"))
    )
    (net (code "102") (name "unconnected-(X1I-1-Pad8)") (class "Default")
      (node (ref "X1") (pin "8") (pinfunction "1_8") (pintype "passive"))
    )
    (net (code "103") (name "unconnected-(X1J-1-Pad9)") (class "Default")
      (node (ref "X1") (pin "9") (pinfunction "1_9") (pintype "passive"))
    )
    (net (code "104") (name "unconnected-(X4-Pad1)") (class "Default")
      (node (ref "X4") (pin "1") (pinfunction "1_1") (pintype "passive"))
    )
    (net (code "105") (name "unconnected-(X4B-1-Pad10)") (class "Default")
      (node (ref "X4") (pin "10") (pinfunction "1_10") (pintype "passive"))
    )
    (net (code "106") (name "unconnected-(X4C-1-Pad2)") (class "Default")
      (node (ref "X4") (pin "2") (pinfunction "1_2") (pintype "passive"))
    )
    (net (code "107") (name "unconnected-(X4D-1-Pad3)") (class "Default")
      (node (ref "X4") (pin "3") (pinfunction "1_3") (pintype "passive"))
    )
    (net (code "108") (name "unconnected-(X4E-1-Pad4)") (class "Default")
      (node (ref "X4") (pin "4") (pinfunction "1_4") (pintype "passive"))
    )
    (net (code "109") (name "unconnected-(X4F-1-Pad5)") (class "Default")
      (node (ref "X4") (pin "5") (pinfunction "1_5") (pintype "passive"))
    )
    (net (code "110") (name "unconnected-(X4G-1-Pad6)") (class "Default")
      (node (ref "X4") (pin "6") (pinfunction "1_6") (pintype "passive"))
    )
    (net (code "111") (name "unconnected-(X4H-1-Pad7)") (class "Default")
      (node (ref "X4") (pin "7") (pinfunction "1_7") (pintype "passive"))
    )
    (net (code "112") (name "unconnected-(X4I-1-Pad8)") (class "Default")
      (node (ref "X4") (pin "8") (pinfunction "1_8") (pintype "passive"))
    )
    (net (code "113") (name "unconnected-(X4J-1-Pad9)") (class "Default")
      (node (ref "X4") (pin "9") (pinfunction "1_9") (pintype "passive"))
    )
  )
)
